# Sheet1.net
KiCad netlist of a schematic drawn in Altium Designer
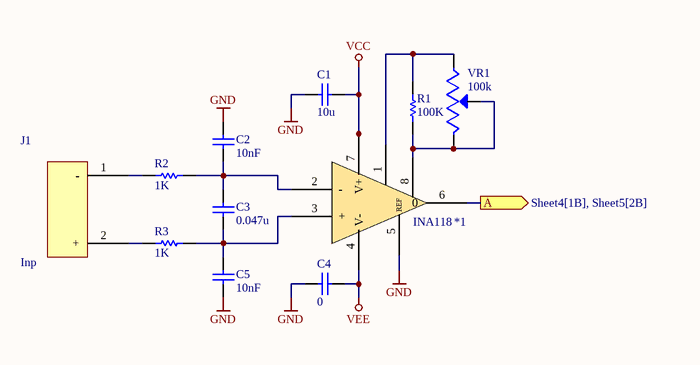
[diagram p0: Sheet1.SchDoc]

(export (version "E")
  (design (tool "Eeschema 10.0.6"))
  (components
    (comp (ref "*1")
      (value "INA118")
      (footprint "SOIC127P599X175-8N")
      (libsource (lib "Schlib1") (part "INA118"))
    )
    (comp (ref "C1")
      (value "10u")
      (footprint "CAPC2012X150N")
      (description "Capacitor")
      (libsource (lib "Simulation Generic Components") (part "Capacitor"))
    )
    (comp (ref "C2")
      (value "10nF")
      (footprint "CAPC2012X150N")
      (description "Capacitor")
      (libsource (lib "Simulation Generic Components") (part "Capacitor"))
    )
    (comp (ref "C3")
      (value "0.047u")
      (footprint "CAPC2012X150N")
      (description "Capacitor")
      (libsource (lib "Simulation Generic Components") (part "Capacitor"))
    )
    (comp (ref "C4")
      (value "0")
      (footprint "CAPC2012X150N")
      (description "Capacitor")
      (libsource (lib "Simulation Generic Components") (part "Capacitor"))
    )
    (comp (ref "C5")
      (value "10nF")
      (footprint "CAPC2012X150N")
      (description "Capacitor")
      (libsource (lib "Simulation Generic Components") (part "Capacitor"))
    )
    (comp (ref "J1")
      (value "Inp")
      (footprint "JST_B2B-XH-A_(LF)(SN)")
      (libsource (lib "Schlib1") (part "Inp"))
    )
    (comp (ref "R1")
      (value "100K")
      (footprint "RES_ERA6AHD330V")
      (description "Resistor")
      (libsource (lib "Simulation Generic Components") (part "Resistor"))
    )
    (comp (ref "R2")
      (value "1K")
      (footprint "RES_ERA6AHD330V")
      (description "Resistor")
      (libsource (lib "Simulation Generic Components") (part "Resistor"))
    )
    (comp (ref "R3")
      (value "1K")
      (footprint "RES_ERA6AHD330V")
      (description "Resistor")
      (libsource (lib "Simulation Generic Components") (part "Resistor"))
    )
    (comp (ref "VR1")
      (value "100k")
      (footprint "TRIM_3296W-1-103RLF")
      (description "Trimmer, Cermet, Rest 10 Kilohms, PCB, 25 Turns, Pwr-Rtg 0.5W ¦ Bourns 3296W-1-103RLF")
      (fields (field (name "MF") "Bourns") (field (name "MP") "3296W-1-103RLF"))
      (libsource (lib "3296W-1-103RLF") (part "3296W-1-103RLF"))
    )
  )
  (nets
    (net (code "1") (name "/A") (class "Default")
      (node (ref "*1") (pin "6") (pinfunction "0_6") (pintype "passive"))
    )
    (net (code "2") (name "GND") (class "Default")
      (node (ref "*1") (pin "5") (pinfunction "REF_5") (pintype "passive"))
      (node (ref "C1") (pin "2") (pinfunction "2_2") (pintype "passive"))
      (node (ref "C2") (pin "2") (pinfunction "2_2") (pintype "passive"))
      (node (ref "C4") (pin "2") (pinfunction "2_2") (pintype "passive"))
      (node (ref "C5") (pin "1") (pinfunction "1_1") (pintype "passive"))
    )
    (net (code "3") (name "Net-(*1-+)") (class "Default")
      (node (ref "*1") (pin "3") (pinfunction "+_3") (pintype "passive"))
      (node (ref "C3") (pin "1") (pinfunction "1_1") (pintype "passive"))
      (node (ref "C5") (pin "2") (pinfunction "2_2") (pintype "passive"))
      (node (ref "R3") (pin "2") (pinfunction "2_2") (pintype "passive"))
    )
    (net (code "4") (name "Net-(*1--)") (class "Default")
      (node (ref "*1") (pin "2") (pinfunction "-_2") (pintype "passive"))
      (node (ref "C2") (pin "1") (pinfunction "1_1") (pintype "passive"))
      (node (ref "C3") (pin "2") (pinfunction "2_2") (pintype "passive"))
      (node (ref "R2") (pin "2") (pinfunction "2_2") (pintype "passive"))
    )
    (net (code "5") (name "Net-(J1-+)") (class "Default")
      (node (ref "J1") (pin "2") (pinfunction "+_2") (pintype "passive"))
      (node (ref "R3") (pin "1") (pinfunction "1_1") (pintype "passive"))
    )
    (net (code "6") (name "Net-(J1--)") (class "Default")
      (node (ref "J1") (pin "1") (pinfunction "-_1") (pintype "passive"))
      (node (ref "R2") (pin "1") (pinfunction "1_1") (pintype "passive"))
    )
    (net (code "7") (name "Net-(VR1-CCW)") (class "Default")
      (node (ref "*1") (pin "1") (pintype "passive"))
      (node (ref "R1") (pin "2") (pinfunction "2_2") (pintype "passive"))
      (node (ref "VR1") (pin "1") (pinfunction "CCW_1") (pintype "passive"))
    )
    (net (code "8") (name "Net-(VR1-CW)") (class "Default")
      (node (ref "*1") (pin "8") (pintype "passive"))
      (node (ref "R1") (pin "1") (pinfunction "1_1") (pintype "passive"))
      (node (ref "VR1") (pin "2") (pinfunction "WIPER_2") (pintype "passive"))
      (node (ref "VR1") (pin "3") (pinfunction "CW_3") (pintype "passive"))
    )
    (net (code "9") (name "VCC") (class "Default")
      (node (ref "*1") (pin "7") (pinfunction "V+_7") (pintype "passive"))
      (node (ref "C1") (pin "1") (pinfunction "1_1") (pintype "passive"))
    )
    (net (code "10") (name "VEE") (class "Default")
      (node (ref "*1") (pin "4") (pinfunction "V-_4") (pintype "passive"))
      (node (ref "C4") (pin "1") (pinfunction "1_1") (pintype "passive"))
    )
  )
)
